# Schematic1.net
KiCad netlist of a schematic drawn in Altium Designer
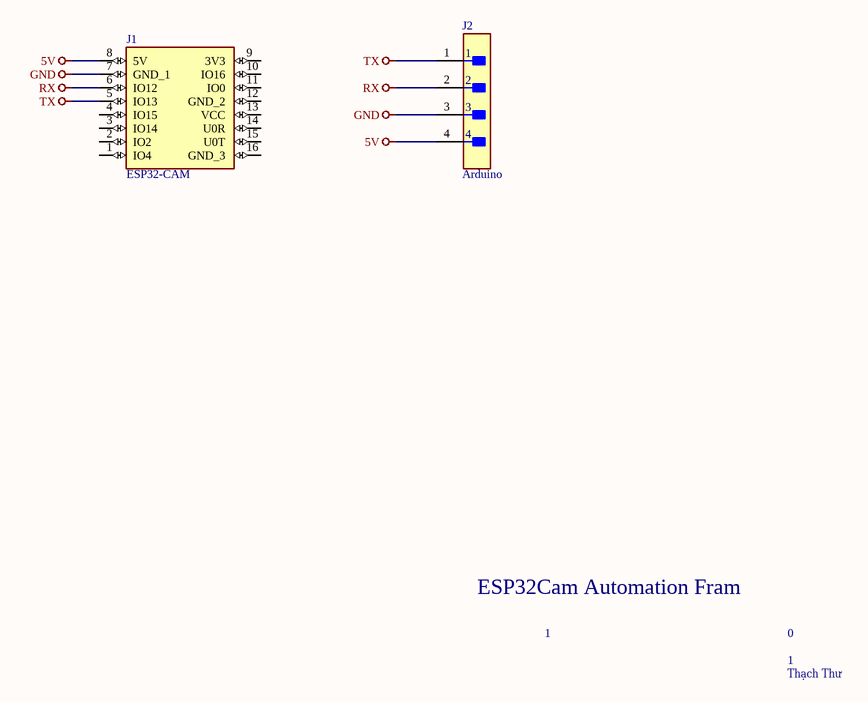
[diagram p0: Schematic1.SchDoc]

(export (version "E")
  (design (tool "Eeschema 10.0.6"))
  (components
    (comp (ref "J1")
      (value "ESP32-CAM")
      (footprint "ESP32-CAM")
      (fields (field (name "MF") "AI-Thinker"))
      (libsource (lib "ESP32-CAM") (part "ESP32-CAM"))
    )
    (comp (ref "J2")
      (value "Arduino")
      (footprint "FP-1881464-MFG")
      (description "TERM BLOCK HDR 4POS 90DEG 2.5MM")
      (fields
        (field (name "MANUFACTURER PART NUMBER") "1881464")
        (field (name "OCTOPART") "https://octopart.com/1881464-phoenix+contact-62398")
      )
      (libsource (lib "Altium Content Vault") (part "299a8cea1bdcbc3624fe62c390fa72c"))
    )
  )
  (nets
    (net (code "1") (name "5V") (class "Default")
      (node (ref "J1") (pin "8") (pinfunction "5V_8") (pintype "bidirectional"))
      (node (ref "J2") (pin "4") (pinfunction "4_4") (pintype "passive"))
    )
    (net (code "2") (name "GND") (class "Default")
      (node (ref "J1") (pin "7") (pinfunction "GND_1_7") (pintype "bidirectional"))
      (node (ref "J2") (pin "3") (pinfunction "3_3") (pintype "passive"))
    )
    (net (code "3") (name "RX") (class "Default")
      (node (ref "J1") (pin "6") (pinfunction "IO12_6") (pintype "bidirectional"))
      (node (ref "J2") (pin "2") (pinfunction "2_2") (pintype "passive"))
    )
    (net (code "4") (name "TX") (class "Default")
      (node (ref "J1") (pin "5") (pinfunction "IO13_5") (pintype "bidirectional"))
      (node (ref "J2") (pin "1") (pinfunction "1_1") (pintype "passive"))
    )
    (net (code "5") (name "unconnected-(J1-3V3-Pad9)") (class "Default")
      (node (ref "J1") (pin "9") (pinfunction "3V3_9") (pintype "bidirectional"))
    )
    (net (code "6") (name "unconnected-(J1-GND_2-Pad12)") (class "Default")
      (node (ref "J1") (pin "12") (pinfunction "GND_2_12") (pintype "bidirectional"))
    )
    (net (code "7") (name "unconnected-(J1-GND_3-Pad16)") (class "Default")
      (node (ref "J1") (pin "16") (pinfunction "GND_3_16") (pintype "bidirectional"))
    )
    (net (code "8") (name "unconnected-(J1-IO0-Pad11)") (class "Default")
      (node (ref "J1") (pin "11") (pinfunction "IO0_11") (pintype "bidirectional"))
    )
    (net (code "9") (name "unconnected-(J1-IO2-Pad2)") (class "Default")
      (node (ref "J1") (pin "2") (pinfunction "IO2_2") (pintype "bidirectional"))
    )
    (net (code "10") (name "unconnected-(J1-IO4-Pad1)") (class "Default")
      (node (ref "J1") (pin "1") (pinfunction "IO4_1") (pintype "bidirectional"))
    )
    (net (code "11") (name "unconnected-(J1-IO14-Pad3)") (class "Default")
      (node (ref "J1") (pin "3") (pinfunction "IO14_3") (pintype "bidirectional"))
    )
    (net (code "12") (name "unconnected-(J1-IO15-Pad4)") (class "Default")
      (node (ref "J1") (pin "4") (pinfunction "IO15_4") (pintype "bidirectional"))
    )
    (net (code "13") (name "unconnected-(J1-IO16-Pad10)") (class "Default")
      (node (ref "J1") (pin "10") (pinfunction "IO16_10") (pintype "bidirectional"))
    )
    (net (code "14") (name "unconnected-(J1-U0R-Pad14)") (class "Default")
      (node (ref "J1") (pin "14") (pinfunction "U0R_14") (pintype "bidirectional"))
    )
    (net (code "15") (name "unconnected-(J1-U0T-Pad15)") (class "Default")
      (node (ref "J1") (pin "15") (pinfunction "U0T_15") (pintype "bidirectional"))
    )
    (net (code "16") (name "unconnected-(J1-VCC-Pad13)") (class "Default")
      (node (ref "J1") (pin "13") (pinfunction "VCC_13") (pintype "bidirectional"))
    )
  )
)
